# FEP_of_Exodia_ver2.net
KiCad netlist of a schematic drawn in EAGLE
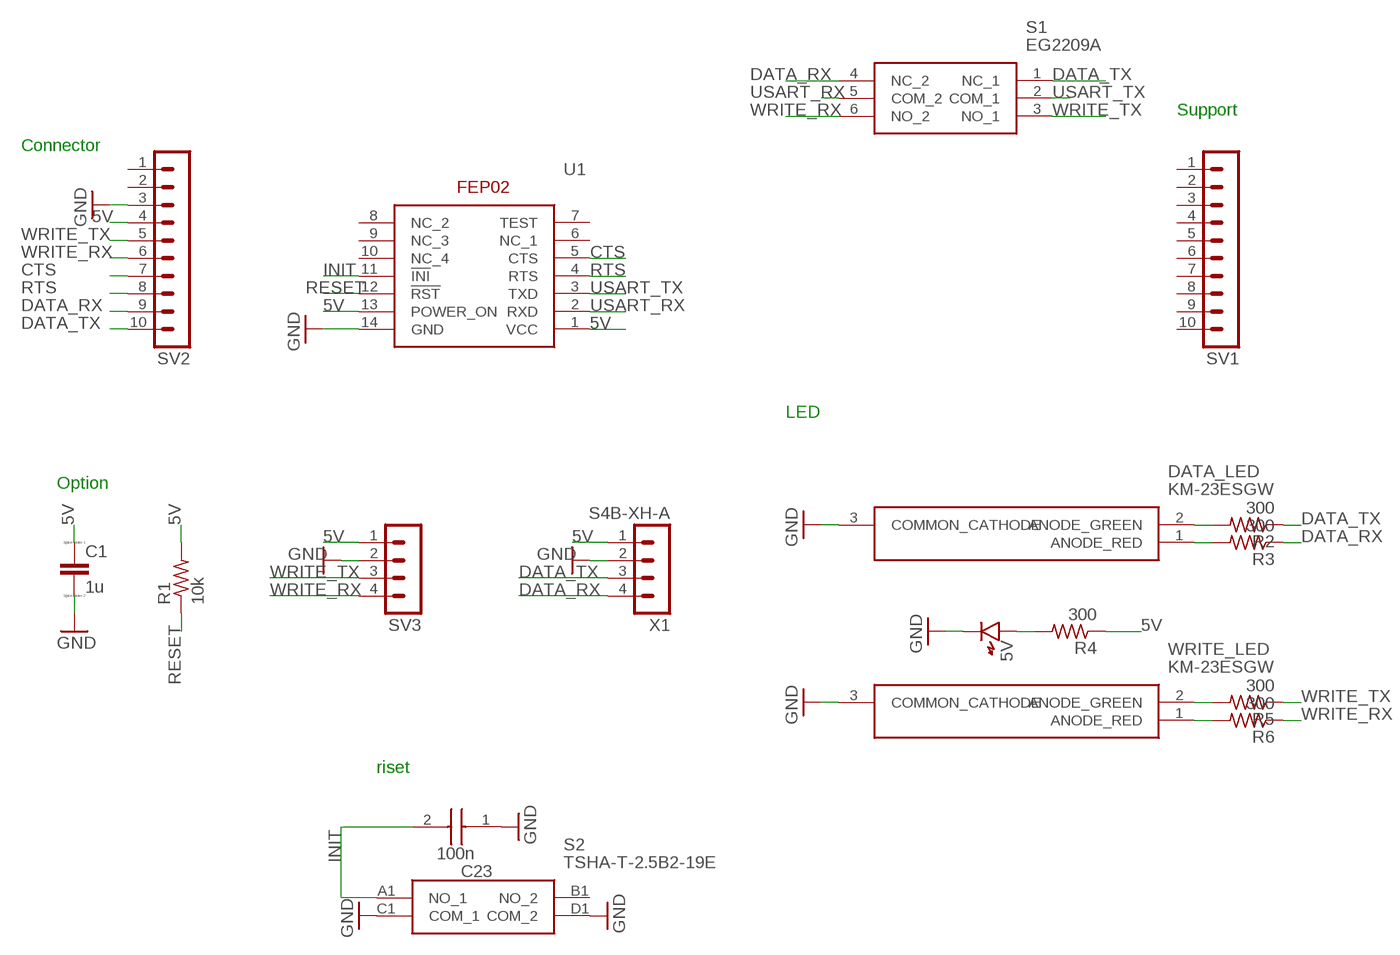
[diagram p0: schematic, sheet 1]

(export (version "E")
  (design (tool "Eeschema 10.0.6"))
  (components
    (comp (ref "5V")
      (value "LED1608")
      (footprint "eagle-import:LED1608")
      (libsource (lib "eagle-import") (part "LED1608"))
    )
    (comp (ref "C1")
      (value "1u")
      (footprint "eagle-import:C0603")
      (libsource (lib "eagle-import") (part "CC0603"))
    )
    (comp (ref "C23")
      (value "100n")
      (footprint "eagle-import:CAPC1709X100N")
      (fields
        (field (name "MANUFACTURER_PART_NUMBER") "AMK107BBJ476MA-RE")
        (field (name "MOUSER_PART_NUMBER") "963-AMK107BBJ476MARE")
        (field (name "RS_PART_NUMBER") "1843762P")
      )
      (libsource (lib "eagle-import") (part "AMK107BBJ476MA-RE"))
    )
    (comp (ref "DATA_LED")
      (value "KM-23ESGW")
      (footprint "eagle-import:SOT-23")
      (libsource (lib "eagle-import") (part "KM-23ESGW"))
    )
    (comp (ref "R1")
      (value "10k")
      (footprint "eagle-import:R0603")
      (libsource (lib "eagle-import") (part "R-US_R0603"))
    )
    (comp (ref "R2")
      (value "300")
      (footprint "eagle-import:R0603")
      (libsource (lib "eagle-import") (part "R-US_R0603"))
    )
    (comp (ref "R3")
      (value "300")
      (footprint "eagle-import:R0603")
      (libsource (lib "eagle-import") (part "R-US_R0603"))
    )
    (comp (ref "R4")
      (value "300")
      (footprint "eagle-import:R0603")
      (libsource (lib "eagle-import") (part "R-US_R0603"))
    )
    (comp (ref "R5")
      (value "300")
      (footprint "eagle-import:R0603")
      (libsource (lib "eagle-import") (part "R-US_R0603"))
    )
    (comp (ref "R6")
      (value "300")
      (footprint "eagle-import:R0603")
      (libsource (lib "eagle-import") (part "R-US_R0603"))
    )
    (comp (ref "S1")
      (value "EG2209A")
      (footprint "eagle-import:EG2209A")
      (fields (field (name "MOUSER_PART_NUMBER") "612-EG2209A"))
      (libsource (lib "eagle-import") (part "EG2209A"))
    )
    (comp (ref "S2")
      (value "TSHA-T-2.5B2-19E")
      (footprint "eagle-import:TSHAT25B219E")
      (libsource (lib "eagle-import") (part "TSHA-T-2.5B2-19E"))
    )
    (comp (ref "SV1")
      (value "MA10-1")
      (footprint "eagle-import:MA10-1")
      (libsource (lib "eagle-import") (part "MA10-1"))
    )
    (comp (ref "SV2")
      (value "MA10-1")
      (footprint "eagle-import:MA10-1")
      (libsource (lib "eagle-import") (part "MA10-1"))
    )
    (comp (ref "SV3")
      (value "MA04-1")
      (footprint "eagle-import:MA04-1")
      (libsource (lib "eagle-import") (part "MA04-1"))
    )
    (comp (ref "U1")
      (value "FEP02")
      (footprint "eagle-import:FEP02")
      (libsource (lib "eagle-import") (part "FEP02"))
    )
    (comp (ref "WRITE_LED")
      (value "KM-23ESGW")
      (footprint "eagle-import:SOT-23")
      (libsource (lib "eagle-import") (part "KM-23ESGW"))
    )
    (comp (ref "X1")
      (value "S4B-XH-A")
      (footprint "eagle-import:S4B-XH-A")
      (libsource (lib "eagle-import") (part "S4B-XH-A"))
    )
  )
  (nets
    (net (code "1") (name "/5V") (class "Default")
      (node (ref "C1") (pin "1") (pinfunction "1_1") (pintype "passive"))
      (node (ref "R1") (pin "2") (pinfunction "2_2") (pintype "passive"))
      (node (ref "R4") (pin "1") (pinfunction "1_1") (pintype "passive"))
      (node (ref "SV2") (pin "4") (pinfunction "4_4") (pintype "passive"))
      (node (ref "SV3") (pin "1") (pinfunction "1_1") (pintype "passive"))
      (node (ref "U1") (pin "1") (pinfunction "VCC_1") (pintype "bidirectional"))
      (node (ref "U1") (pin "13") (pinfunction "POWER_ON_13") (pintype "bidirectional"))
      (node (ref "X1") (pin "1") (pinfunction "1_1") (pintype "passive"))
    )
    (net (code "2") (name "/CTS") (class "Default")
      (node (ref "SV2") (pin "7") (pinfunction "7_7") (pintype "passive"))
      (node (ref "U1") (pin "5") (pinfunction "CTS_5") (pintype "bidirectional"))
    )
    (net (code "3") (name "/DATA_RX") (class "Default")
      (node (ref "R3") (pin "1") (pinfunction "1_1") (pintype "passive"))
      (node (ref "S1") (pin "4") (pinfunction "NC_2_4") (pintype "bidirectional"))
      (node (ref "SV2") (pin "9") (pinfunction "9_9") (pintype "passive"))
      (node (ref "X1") (pin "4") (pinfunction "4_4") (pintype "passive"))
    )
    (net (code "4") (name "/DATA_TX") (class "Default")
      (node (ref "R2") (pin "1") (pinfunction "1_1") (pintype "passive"))
      (node (ref "S1") (pin "1") (pinfunction "NC_1_1") (pintype "bidirectional"))
      (node (ref "SV2") (pin "10") (pinfunction "10_10") (pintype "passive"))
      (node (ref "X1") (pin "3") (pinfunction "3_3") (pintype "passive"))
    )
    (net (code "5") (name "/INIT") (class "Default")
      (node (ref "C23") (pin "2") (pinfunction "2_2") (pintype "bidirectional"))
      (node (ref "S2") (pin "A1") (pinfunction "NO_1_A1") (pintype "bidirectional"))
      (node (ref "U1") (pin "11") (pinfunction "~{INI}_11") (pintype "bidirectional"))
    )
    (net (code "6") (name "/RESET") (class "Default")
      (node (ref "R1") (pin "1") (pinfunction "1_1") (pintype "passive"))
      (node (ref "U1") (pin "12") (pinfunction "~{RST}_12") (pintype "bidirectional"))
    )
    (net (code "7") (name "/RTS") (class "Default")
      (node (ref "SV2") (pin "8") (pinfunction "8_8") (pintype "passive"))
      (node (ref "U1") (pin "4") (pinfunction "RTS_4") (pintype "bidirectional"))
    )
    (net (code "8") (name "/USART_RX") (class "Default")
      (node (ref "S1") (pin "5") (pinfunction "COM_2_5") (pintype "bidirectional"))
      (node (ref "U1") (pin "2") (pinfunction "RXD_2") (pintype "bidirectional"))
    )
    (net (code "9") (name "/USART_TX") (class "Default")
      (node (ref "S1") (pin "2") (pinfunction "COM_1_2") (pintype "bidirectional"))
      (node (ref "U1") (pin "3") (pinfunction "TXD_3") (pintype "bidirectional"))
    )
    (net (code "10") (name "/WRITE_RX") (class "Default")
      (node (ref "R6") (pin "1") (pinfunction "1_1") (pintype "passive"))
      (node (ref "S1") (pin "6") (pinfunction "NO_2_6") (pintype "bidirectional"))
      (node (ref "SV2") (pin "6") (pinfunction "6_6") (pintype "passive"))
      (node (ref "SV3") (pin "4") (pinfunction "4_4") (pintype "passive"))
    )
    (net (code "11") (name "/WRITE_TX") (class "Default")
      (node (ref "R5") (pin "1") (pinfunction "1_1") (pintype "passive"))
      (node (ref "S1") (pin "3") (pinfunction "NO_1_3") (pintype "bidirectional"))
      (node (ref "SV2") (pin "5") (pinfunction "5_5") (pintype "passive"))
      (node (ref "SV3") (pin "3") (pinfunction "3_3") (pintype "passive"))
    )
    (net (code "12") (name "GND") (class "Default")
      (node (ref "5V") (pin "K") (pinfunction "K_K") (pintype "passive"))
      (node (ref "C1") (pin "2") (pinfunction "2_2") (pintype "passive"))
      (node (ref "C23") (pin "1") (pinfunction "1_1") (pintype "bidirectional"))
      (node (ref "DATA_LED") (pin "3") (pinfunction "COMMON_CATHODE_3") (pintype "bidirectional"))
      (node (ref "S2") (pin "C1") (pinfunction "COM_1_C1") (pintype "bidirectional"))
      (node (ref "S2") (pin "D1") (pinfunction "COM_2_D1") (pintype "bidirectional"))
      (node (ref "SV2") (pin "3") (pinfunction "3_3") (pintype "passive"))
      (node (ref "SV3") (pin "2") (pinfunction "2_2") (pintype "passive"))
      (node (ref "U1") (pin "14") (pinfunction "GND_14") (pintype "bidirectional"))
      (node (ref "WRITE_LED") (pin "3") (pinfunction "COMMON_CATHODE_3") (pintype "bidirectional"))
      (node (ref "X1") (pin "2") (pinfunction "2_2") (pintype "passive"))
    )
    (net (code "13") (name "Net-(5V-PadA)") (class "Default")
      (node (ref "5V") (pin "A") (pinfunction "A_A") (pintype "passive"))
      (node (ref "R4") (pin "2") (pinfunction "2_2") (pintype "passive"))
    )
    (net (code "14") (name "Net-(DATA_LED-ANODE_GREEN)") (class "Default")
      (node (ref "DATA_LED") (pin "2") (pinfunction "ANODE_GREEN_2") (pintype "bidirectional"))
      (node (ref "R2") (pin "2") (pinfunction "2_2") (pintype "passive"))
    )
    (net (code "15") (name "Net-(DATA_LED-ANODE_RED)") (class "Default")
      (node (ref "DATA_LED") (pin "1") (pinfunction "ANODE_RED_1") (pintype "bidirectional"))
      (node (ref "R3") (pin "2") (pinfunction "2_2") (pintype "passive"))
    )
    (net (code "16") (name "Net-(WRITE_LED-ANODE_GREEN)") (class "Default")
      (node (ref "R5") (pin "2") (pinfunction "2_2") (pintype "passive"))
      (node (ref "WRITE_LED") (pin "2") (pinfunction "ANODE_GREEN_2") (pintype "bidirectional"))
    )
    (net (code "17") (name "Net-(WRITE_LED-ANODE_RED)") (class "Default")
      (node (ref "R6") (pin "2") (pinfunction "2_2") (pintype "passive"))
      (node (ref "WRITE_LED") (pin "1") (pinfunction "ANODE_RED_1") (pintype "bidirectional"))
    )
    (net (code "18") (name "unconnected-(S2-NO_2-PadB1)") (class "Default")
      (node (ref "S2") (pin "B1") (pinfunction "NO_2_B1") (pintype "bidirectional"))
    )
    (net (code "19") (name "unconnected-(SV1-Pad1)") (class "Default")
      (node (ref "SV1") (pin "1") (pinfunction "1_1") (pintype "passive"))
    )
    (net (code "20") (name "unconnected-(SV1-Pad2)") (class "Default")
      (node (ref "SV1") (pin "2") (pinfunction "2_2") (pintype "passive"))
    )
    (net (code "21") (name "unconnected-(SV1-Pad3)") (class "Default")
      (node (ref "SV1") (pin "3") (pinfunction "3_3") (pintype "passive"))
    )
    (net (code "22") (name "unconnected-(SV1-Pad4)") (class "Default")
      (node (ref "SV1") (pin "4") (pinfunction "4_4") (pintype "passive"))
    )
    (net (code "23") (name "unconnected-(SV1-Pad5)") (class "Default")
      (node (ref "SV1") (pin "5") (pinfunction "5_5") (pintype "passive"))
    )
    (net (code "24") (name "unconnected-(SV1-Pad6)") (class "Default")
      (node (ref "SV1") (pin "6") (pinfunction "6_6") (pintype "passive"))
    )
    (net (code "25") (name "unconnected-(SV1-Pad7)") (class "Default")
      (node (ref "SV1") (pin "7") (pinfunction "7_7") (pintype "passive"))
    )
    (net (code "26") (name "unconnected-(SV1-Pad8)") (class "Default")
      (node (ref "SV1") (pin "8") (pinfunction "8_8") (pintype "passive"))
    )
    (net (code "27") (name "unconnected-(SV1-Pad9)") (class "Default")
      (node (ref "SV1") (pin "9") (pinfunction "9_9") (pintype "passive"))
    )
    (net (code "28") (name "unconnected-(SV1-Pad10)") (class "Default")
      (node (ref "SV1") (pin "10") (pinfunction "10_10") (pintype "passive"))
    )
    (net (code "29") (name "unconnected-(SV2-Pad1)") (class "Default")
      (node (ref "SV2") (pin "1") (pinfunction "1_1") (pintype "passive"))
    )
    (net (code "30") (name "unconnected-(SV2-Pad2)") (class "Default")
      (node (ref "SV2") (pin "2") (pinfunction "2_2") (pintype "passive"))
    )
    (net (code "31") (name "unconnected-(U1-NC_1-Pad6)") (class "Default")
      (node (ref "U1") (pin "6") (pinfunction "NC_1_6") (pintype "bidirectional"))
    )
    (net (code "32") (name "unconnected-(U1-NC_2-Pad8)") (class "Default")
      (node (ref "U1") (pin "8") (pinfunction "NC_2_8") (pintype "bidirectional"))
    )
    (net (code "33") (name "unconnected-(U1-NC_3-Pad9)") (class "Default")
      (node (ref "U1") (pin "9") (pinfunction "NC_3_9") (pintype "bidirectional"))
    )
    (net (code "34") (name "unconnected-(U1-NC_4-Pad10)") (class "Default")
      (node (ref "U1") (pin "10") (pinfunction "NC_4_10") (pintype "bidirectional"))
    )
    (net (code "35") (name "unconnected-(U1-TEST-Pad7)") (class "Default")
      (node (ref "U1") (pin "7") (pinfunction "TEST_7") (pintype "bidirectional"))
    )
  )
)
